# OmniBot_motor_driver.net
KiCad netlist of a schematic drawn in EAGLE
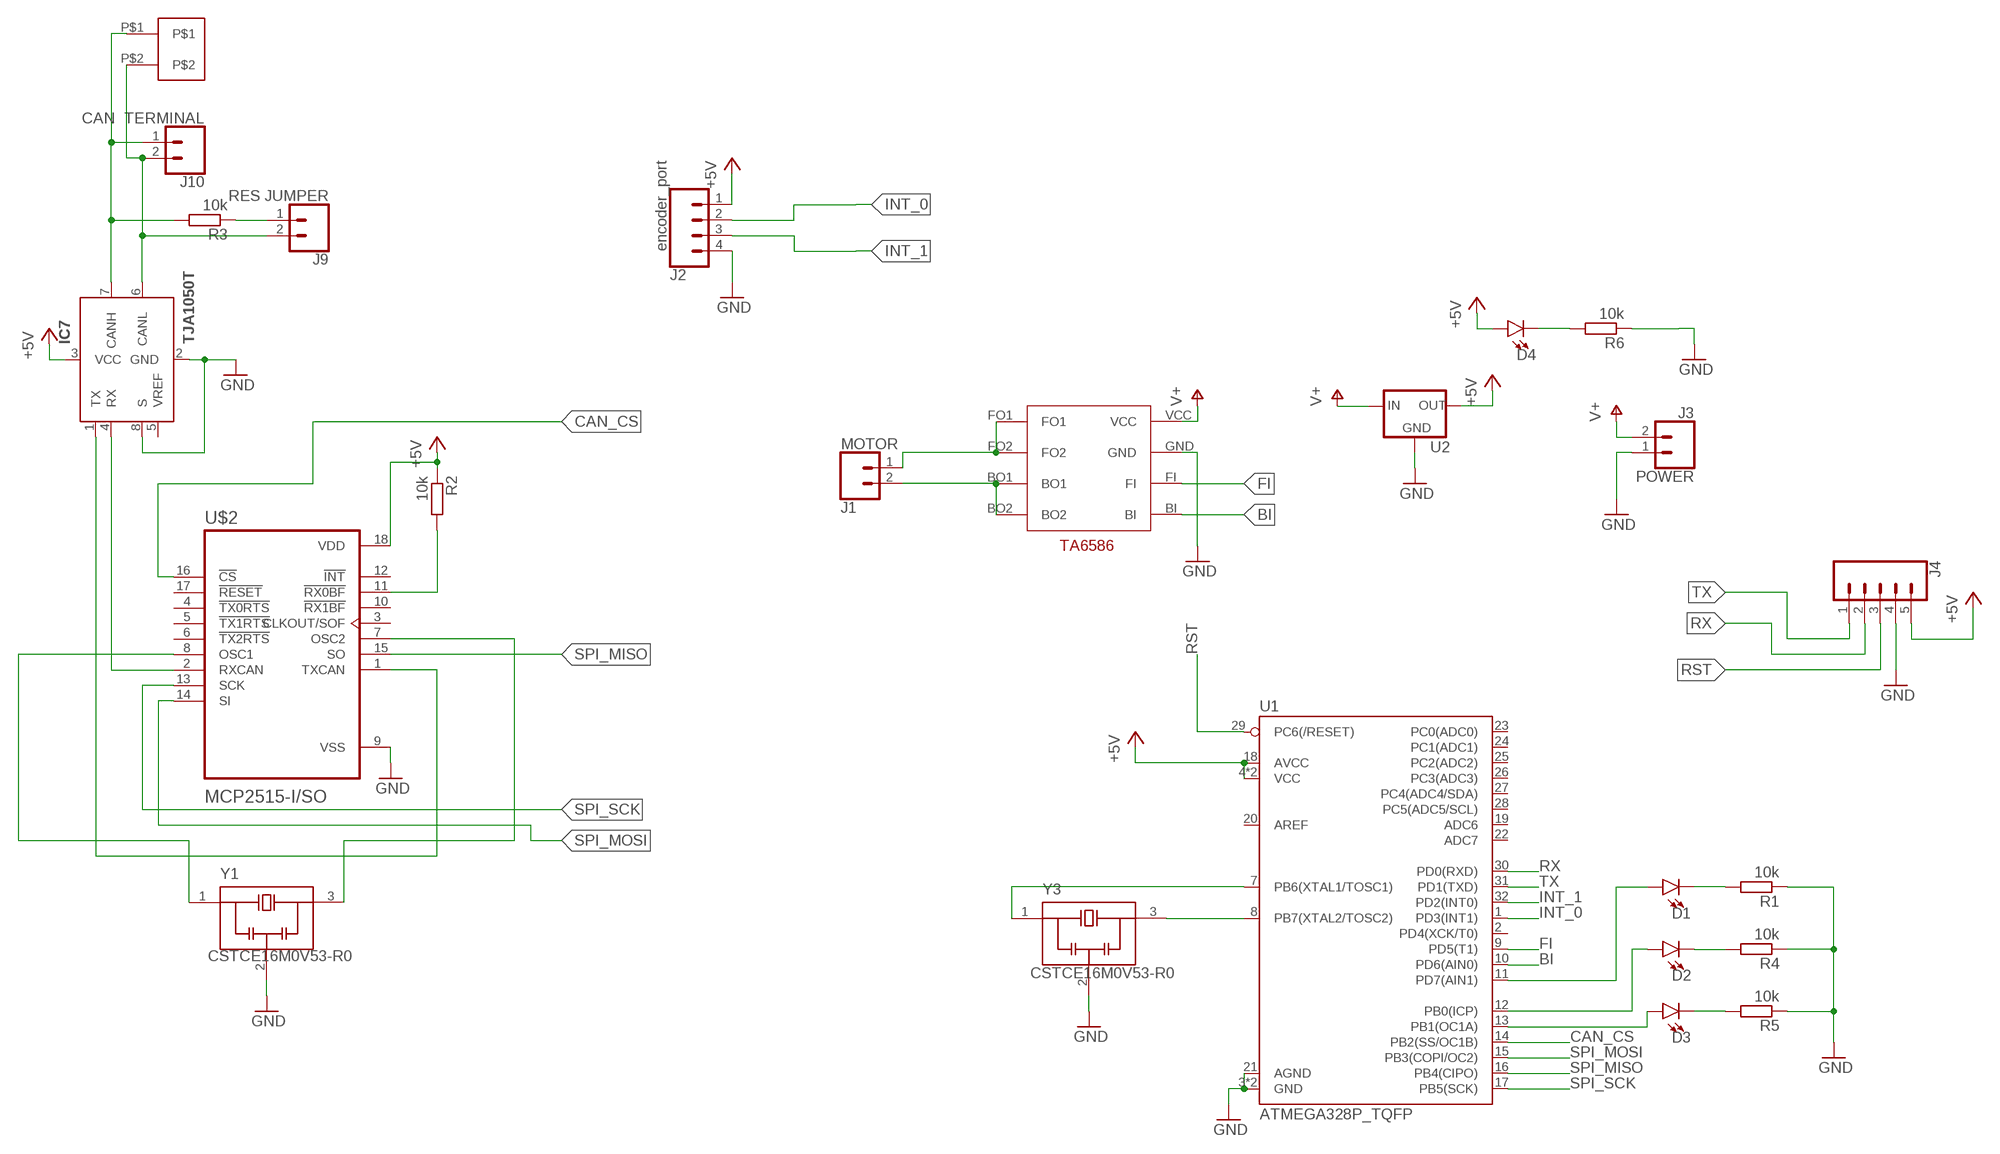
[diagram p0: schematic, sheet 1]

(export (version "E")
  (design (tool "Eeschema 10.0.6"))
  (components
    (comp (ref "D1")
      (value "LED3MM")
      (footprint "eagle-import:LED_3MM")
      (libsource (lib "eagle-import") (part "LED3MM"))
    )
    (comp (ref "D2")
      (value "LED3MM")
      (footprint "eagle-import:LED_3MM")
      (libsource (lib "eagle-import") (part "LED3MM"))
    )
    (comp (ref "D3")
      (value "LED3MM")
      (footprint "eagle-import:LED_3MM")
      (libsource (lib "eagle-import") (part "LED3MM"))
    )
    (comp (ref "D4")
      (value "LED3MM")
      (footprint "eagle-import:LED_3MM")
      (libsource (lib "eagle-import") (part "LED3MM"))
    )
    (comp (ref "IC7")
      (value "TJA1050T")
      (footprint "eagle-import:SOIC8")
      (fields (field (name "MF") "NXP"))
      (libsource (lib "eagle-import") (part "TJA1050T"))
    )
    (comp (ref "J1")
      (value "MOTOR")
      (footprint "eagle-import:SCREWTERMINAL-5MM-2")
      (libsource (lib "eagle-import") (part "CONN_025MM"))
    )
    (comp (ref "J2")
      (value "encoder_port")
      (footprint "eagle-import:MOLEX-1X4")
      (libsource (lib "eagle-import") (part "CONN_04POLAR"))
    )
    (comp (ref "J3")
      (value "POWER")
      (footprint "eagle-import:SCREWTERMINAL-5MM-2")
      (libsource (lib "eagle-import") (part "CONN_025MM"))
    )
    (comp (ref "J4")
      (value "CONN_05PTH")
      (footprint "eagle-import:1X05")
      (libsource (lib "eagle-import") (part "CONN_05PTH"))
    )
    (comp (ref "J9")
      (value "RES JUMPER")
      (footprint "eagle-import:1X02")
      (libsource (lib "eagle-import") (part "CONN_02"))
    )
    (comp (ref "J10")
      (value "CAN TERMINAL")
      (footprint "eagle-import:SCREWTERMINAL-5MM-2")
      (libsource (lib "eagle-import") (part "CONN_025MM"))
    )
    (comp (ref "R1")
      (value "10k")
      (footprint "eagle-import:R0805")
      (libsource (lib "eagle-import") (part "R-EU_R0805"))
    )
    (comp (ref "R2")
      (value "10k")
      (footprint "eagle-import:R0805")
      (libsource (lib "eagle-import") (part "R-EU_R0805"))
    )
    (comp (ref "R3")
      (value "10k")
      (footprint "eagle-import:R0805")
      (libsource (lib "eagle-import") (part "R-EU_R0805"))
    )
    (comp (ref "R4")
      (value "10k")
      (footprint "eagle-import:R0805")
      (libsource (lib "eagle-import") (part "R-EU_R0805"))
    )
    (comp (ref "R5")
      (value "10k")
      (footprint "eagle-import:R0805")
      (libsource (lib "eagle-import") (part "R-EU_R0805"))
    )
    (comp (ref "R6")
      (value "10k")
      (footprint "eagle-import:R0805")
      (libsource (lib "eagle-import") (part "R-EU_R0805"))
    )
    (comp (ref "U$1")
      (value "15EDGRC-3.5-2P")
      (footprint "eagle-import:15EDGRC-3.5-2P-PAK")
      (fields (field (name "MF") "Degson") (field (name "MP") "15EDGRC-3.5/2P"))
      (libsource (lib "eagle-import") (part "15EDGRC-3.5-2P"))
    )
    (comp (ref "U$2")
      (value "MCP2515-I/SO")
      (footprint "eagle-import:SOIC127P1030X265-18N")
      (fields (field (name "MF") "Microchip"))
      (libsource (lib "eagle-import") (part "MCP2515-I/SO"))
    )
    (comp (ref "U$3")
      (value "TA6586")
      (footprint "eagle-import:TA6586-FOOTPRINT")
      (fields (field (name "MF") "Wuxi"))
      (libsource (lib "eagle-import") (part "TA6586"))
    )
    (comp (ref "U1")
      (value "ATMEGA328P_TQFP")
      (footprint "eagle-import:TQFP32-08")
      (libsource (lib "eagle-import") (part "ATMEGA328P_TQFP"))
    )
    (comp (ref "U2")
      (value "V_REG_78XXSINK")
      (footprint "eagle-import:TO220-IGO")
      (libsource (lib "eagle-import") (part "V_REG_78XXSINK"))
    )
    (comp (ref "Y1")
      (value "CSTCE16M0V53-R0")
      (footprint "eagle-import:OSC_CSTCE16M0V53-R0")
      (fields (field (name "MF") "Murata"))
      (libsource (lib "eagle-import") (part "CSTCE16M0V53-R0"))
    )
    (comp (ref "Y3")
      (value "CSTCE16M0V53-R0")
      (footprint "eagle-import:OSC_CSTCE16M0V53-R0")
      (fields (field (name "MF") "Murata"))
      (libsource (lib "eagle-import") (part "CSTCE16M0V53-R0"))
    )
  )
  (nets
    (net (code "1") (name "+5V") (class "Default")
      (node (ref "D4") (pin "A") (pinfunction "A_A") (pintype "passive"))
      (node (ref "IC7") (pin "3") (pinfunction "VCC_3") (pintype "input"))
      (node (ref "J2") (pin "1") (pinfunction "1_1") (pintype "passive"))
      (node (ref "J4") (pin "5") (pinfunction "5_5") (pintype "passive"))
      (node (ref "R2") (pin "1") (pinfunction "1_1") (pintype "passive"))
      (node (ref "U$2") (pin "18") (pinfunction "VDD_18") (pintype "power_in"))
      (node (ref "U1") (pin "18") (pinfunction "AVCC_18") (pintype "bidirectional"))
      (node (ref "U1") (pin "4") (pinfunction "VCC_4") (pintype "bidirectional"))
      (node (ref "U1") (pin "6") (pinfunction "VCC_6") (pintype "bidirectional"))
      (node (ref "U2") (pin "OUT") (pinfunction "OUT_OUT") (pintype "passive"))
    )
    (net (code "2") (name "BI") (class "Default")
      (node (ref "U$3") (pin "BI") (pinfunction "BI_BI") (pintype "bidirectional"))
      (node (ref "U1") (pin "10") (pinfunction "PD6(AIN0)_10") (pintype "bidirectional"))
    )
    (net (code "3") (name "CAN_CS") (class "Default")
      (node (ref "U$2") (pin "16") (pinfunction "~{CS}_16") (pintype "input"))
      (node (ref "U1") (pin "14") (pinfunction "PB2(SS/OC1B)_14") (pintype "bidirectional"))
    )
    (net (code "4") (name "FI") (class "Default")
      (node (ref "U$3") (pin "FI") (pinfunction "FI_FI") (pintype "bidirectional"))
      (node (ref "U1") (pin "9") (pinfunction "PD5(T1)_9") (pintype "bidirectional"))
    )
    (net (code "5") (name "GND") (class "Default")
      (node (ref "IC7") (pin "2") (pinfunction "GND_2") (pintype "power_in"))
      (node (ref "IC7") (pin "8") (pinfunction "S_8") (pintype "input"))
      (node (ref "J2") (pin "4") (pinfunction "4_4") (pintype "passive"))
      (node (ref "J3") (pin "1") (pinfunction "1_1") (pintype "passive"))
      (node (ref "J4") (pin "4") (pinfunction "4_4") (pintype "passive"))
      (node (ref "R1") (pin "1") (pinfunction "1_1") (pintype "passive"))
      (node (ref "R4") (pin "1") (pinfunction "1_1") (pintype "passive"))
      (node (ref "R5") (pin "1") (pinfunction "1_1") (pintype "passive"))
      (node (ref "R6") (pin "1") (pinfunction "1_1") (pintype "passive"))
      (node (ref "U$2") (pin "9") (pinfunction "VSS_9") (pintype "power_in"))
      (node (ref "U$3") (pin "GND") (pinfunction "GND_GND") (pintype "bidirectional"))
      (node (ref "U1") (pin "21") (pinfunction "AGND_21") (pintype "bidirectional"))
      (node (ref "U1") (pin "3") (pinfunction "GND_3") (pintype "bidirectional"))
      (node (ref "U1") (pin "5") (pinfunction "GND_5") (pintype "bidirectional"))
      (node (ref "U2") (pin "GND") (pinfunction "GND_GND") (pintype "input"))
      (node (ref "Y1") (pin "2") (pinfunction "GND_2") (pintype "power_in"))
      (node (ref "Y3") (pin "2") (pinfunction "GND_2") (pintype "power_in"))
    )
    (net (code "6") (name "INT_0") (class "Default")
      (node (ref "J2") (pin "2") (pinfunction "2_2") (pintype "passive"))
      (node (ref "U1") (pin "1") (pinfunction "PD3(INT1)_1") (pintype "bidirectional"))
    )
    (net (code "7") (name "INT_1") (class "Default")
      (node (ref "J2") (pin "3") (pinfunction "3_3") (pintype "passive"))
      (node (ref "U1") (pin "32") (pinfunction "PD2(INT0)_32") (pintype "bidirectional"))
    )
    (net (code "8") (name "Net-(D1-C)") (class "Default")
      (node (ref "D1") (pin "K") (pinfunction "C_K") (pintype "passive"))
      (node (ref "R1") (pin "2") (pinfunction "2_2") (pintype "passive"))
    )
    (net (code "9") (name "Net-(D2-C)") (class "Default")
      (node (ref "D2") (pin "K") (pinfunction "C_K") (pintype "passive"))
      (node (ref "R4") (pin "2") (pinfunction "2_2") (pintype "passive"))
    )
    (net (code "10") (name "Net-(D3-C)") (class "Default")
      (node (ref "D3") (pin "K") (pinfunction "C_K") (pintype "passive"))
      (node (ref "R5") (pin "2") (pinfunction "2_2") (pintype "passive"))
    )
    (net (code "11") (name "Net-(D4-C)") (class "Default")
      (node (ref "D4") (pin "K") (pinfunction "C_K") (pintype "passive"))
      (node (ref "R6") (pin "2") (pinfunction "2_2") (pintype "passive"))
    )
    (net (code "12") (name "Net-(IC7-CANH)") (class "Default")
      (node (ref "IC7") (pin "7") (pinfunction "CANH_7") (pintype "bidirectional"))
      (node (ref "J10") (pin "1") (pinfunction "1_1") (pintype "passive"))
      (node (ref "R3") (pin "2") (pinfunction "2_2") (pintype "passive"))
      (node (ref "U$1") (pin "P$1") (pinfunction "P$1_P$1") (pintype "bidirectional"))
    )
    (net (code "13") (name "Net-(IC7-CANL)") (class "Default")
      (node (ref "IC7") (pin "6") (pinfunction "CANL_6") (pintype "bidirectional"))
      (node (ref "J10") (pin "2") (pinfunction "2_2") (pintype "passive"))
      (node (ref "J9") (pin "2") (pinfunction "2_2") (pintype "passive"))
      (node (ref "U$1") (pin "P$2") (pinfunction "P$2_P$2") (pintype "bidirectional"))
    )
    (net (code "14") (name "Net-(IC7-RX)") (class "Default")
      (node (ref "IC7") (pin "4") (pinfunction "RX_4") (pintype "output"))
      (node (ref "U$2") (pin "2") (pinfunction "RXCAN_2") (pintype "input"))
    )
    (net (code "15") (name "Net-(IC7-TX)") (class "Default")
      (node (ref "IC7") (pin "1") (pinfunction "TX_1") (pintype "input"))
      (node (ref "U$2") (pin "1") (pinfunction "TXCAN_1") (pintype "output"))
    )
    (net (code "16") (name "Net-(J1-Pad1)") (class "Default")
      (node (ref "J1") (pin "1") (pinfunction "1_1") (pintype "passive"))
      (node (ref "U$3") (pin "FO1") (pinfunction "FO1_FO1") (pintype "bidirectional"))
      (node (ref "U$3") (pin "FO2") (pinfunction "FO2_FO2") (pintype "bidirectional"))
    )
    (net (code "17") (name "Net-(J1-Pad2)") (class "Default")
      (node (ref "J1") (pin "2") (pinfunction "2_2") (pintype "passive"))
      (node (ref "U$3") (pin "BO1") (pinfunction "BO1_BO1") (pintype "bidirectional"))
      (node (ref "U$3") (pin "BO2") (pinfunction "BO2_BO2") (pintype "bidirectional"))
    )
    (net (code "18") (name "Net-(J9-Pad1)") (class "Default")
      (node (ref "J9") (pin "1") (pinfunction "1_1") (pintype "passive"))
      (node (ref "R3") (pin "1") (pinfunction "1_1") (pintype "passive"))
    )
    (net (code "19") (name "Net-(U$2-OSC1)") (class "Default")
      (node (ref "U$2") (pin "8") (pinfunction "OSC1_8") (pintype "input"))
      (node (ref "Y1") (pin "1") (pinfunction "IN_1") (pintype "input"))
    )
    (net (code "20") (name "Net-(U$2-OSC2)") (class "Default")
      (node (ref "U$2") (pin "7") (pinfunction "OSC2_7") (pintype "output"))
      (node (ref "Y1") (pin "3") (pinfunction "OUT_3") (pintype "output"))
    )
    (net (code "21") (name "Net-(U$2-~{RX0BF})") (class "Default")
      (node (ref "R2") (pin "2") (pinfunction "2_2") (pintype "passive"))
      (node (ref "U$2") (pin "11") (pinfunction "~{RX0BF}_11") (pintype "output"))
    )
    (net (code "22") (name "Net-(U1-PB0(ICP))") (class "Default")
      (node (ref "D2") (pin "A") (pinfunction "A_A") (pintype "passive"))
      (node (ref "U1") (pin "12") (pinfunction "PB0(ICP)_12") (pintype "bidirectional"))
    )
    (net (code "23") (name "Net-(U1-PB1(OC1A))") (class "Default")
      (node (ref "D3") (pin "A") (pinfunction "A_A") (pintype "passive"))
      (node (ref "U1") (pin "13") (pinfunction "PB1(OC1A)_13") (pintype "bidirectional"))
    )
    (net (code "24") (name "Net-(U1-PB6(XTAL1{slash}TOSC1))") (class "Default")
      (node (ref "U1") (pin "7") (pinfunction "PB6(XTAL1/TOSC1)_7") (pintype "bidirectional"))
      (node (ref "Y3") (pin "1") (pinfunction "IN_1") (pintype "input"))
    )
    (net (code "25") (name "Net-(U1-PB7(XTAL2{slash}TOSC2))") (class "Default")
      (node (ref "U1") (pin "8") (pinfunction "PB7(XTAL2/TOSC2)_8") (pintype "bidirectional"))
      (node (ref "Y3") (pin "3") (pinfunction "OUT_3") (pintype "output"))
    )
    (net (code "26") (name "Net-(U1-PD7(AIN1))") (class "Default")
      (node (ref "D1") (pin "A") (pinfunction "A_A") (pintype "passive"))
      (node (ref "U1") (pin "11") (pinfunction "PD7(AIN1)_11") (pintype "bidirectional"))
    )
    (net (code "27") (name "RST") (class "Default")
      (node (ref "J4") (pin "3") (pinfunction "3_3") (pintype "passive"))
      (node (ref "U1") (pin "29") (pinfunction "PC6(/RESET)_29") (pintype "bidirectional"))
    )
    (net (code "28") (name "RX") (class "Default")
      (node (ref "J4") (pin "2") (pinfunction "2_2") (pintype "passive"))
      (node (ref "U1") (pin "30") (pinfunction "PD0(RXD)_30") (pintype "bidirectional"))
    )
    (net (code "29") (name "SPI_MISO") (class "Default")
      (node (ref "U$2") (pin "15") (pinfunction "SO_15") (pintype "output"))
      (node (ref "U1") (pin "16") (pinfunction "PB4(CIPO)_16") (pintype "bidirectional"))
    )
    (net (code "30") (name "SPI_MOSI") (class "Default")
      (node (ref "U$2") (pin "14") (pinfunction "SI_14") (pintype "input"))
      (node (ref "U1") (pin "15") (pinfunction "PB3(COPI/OC2)_15") (pintype "bidirectional"))
    )
    (net (code "31") (name "SPI_SCK") (class "Default")
      (node (ref "U$2") (pin "13") (pinfunction "SCK_13") (pintype "input"))
      (node (ref "U1") (pin "17") (pinfunction "PB5(SCK)_17") (pintype "bidirectional"))
    )
    (net (code "32") (name "TX") (class "Default")
      (node (ref "J4") (pin "1") (pinfunction "1_1") (pintype "passive"))
      (node (ref "U1") (pin "31") (pinfunction "PD1(TXD)_31") (pintype "bidirectional"))
    )
    (net (code "33") (name "V+") (class "Default")
      (node (ref "J3") (pin "2") (pinfunction "2_2") (pintype "passive"))
      (node (ref "U$3") (pin "VCC") (pinfunction "VCC_VCC") (pintype "bidirectional"))
      (node (ref "U2") (pin "IN") (pinfunction "IN_IN") (pintype "input"))
    )
    (net (code "34") (name "unconnected-(IC7-VREF-Pad5)") (class "Default")
      (node (ref "IC7") (pin "5") (pinfunction "VREF_5") (pintype "output"))
    )
    (net (code "35") (name "unconnected-(U$2-CLKOUT{slash}SOF-Pad3)") (class "Default")
      (node (ref "U$2") (pin "3") (pinfunction "CLKOUT/SOF_3") (pintype "output"))
    )
    (net (code "36") (name "unconnected-(U$2-~{INT}-Pad12)") (class "Default")
      (node (ref "U$2") (pin "12") (pinfunction "~{INT}_12") (pintype "output"))
    )
    (net (code "37") (name "unconnected-(U$2-~{RESET}-Pad17)") (class "Default")
      (node (ref "U$2") (pin "17") (pinfunction "~{RESET}_17") (pintype "input"))
    )
    (net (code "38") (name "unconnected-(U$2-~{RX1BF}-Pad10)") (class "Default")
      (node (ref "U$2") (pin "10") (pinfunction "~{RX1BF}_10") (pintype "output"))
    )
    (net (code "39") (name "unconnected-(U$2-~{TX0RTS}-Pad4)") (class "Default")
      (node (ref "U$2") (pin "4") (pinfunction "~{TX0RTS}_4") (pintype "input"))
    )
    (net (code "40") (name "unconnected-(U$2-~{TX1RTS}-Pad5)") (class "Default")
      (node (ref "U$2") (pin "5") (pinfunction "~{TX1RTS}_5") (pintype "input"))
    )
    (net (code "41") (name "unconnected-(U$2-~{TX2RTS}-Pad6)") (class "Default")
      (node (ref "U$2") (pin "6") (pinfunction "~{TX2RTS}_6") (pintype "input"))
    )
    (net (code "42") (name "unconnected-(U1-ADC6-Pad19)") (class "Default")
      (node (ref "U1") (pin "19") (pinfunction "ADC6_19") (pintype "bidirectional"))
    )
    (net (code "43") (name "unconnected-(U1-ADC7-Pad22)") (class "Default")
      (node (ref "U1") (pin "22") (pinfunction "ADC7_22") (pintype "bidirectional"))
    )
    (net (code "44") (name "unconnected-(U1-AREF-Pad20)") (class "Default")
      (node (ref "U1") (pin "20") (pinfunction "AREF_20") (pintype "bidirectional"))
    )
    (net (code "45") (name "unconnected-(U1-PC0(ADC0)-Pad23)") (class "Default")
      (node (ref "U1") (pin "23") (pinfunction "PC0(ADC0)_23") (pintype "bidirectional"))
    )
    (net (code "46") (name "unconnected-(U1-PC1(ADC1)-Pad24)") (class "Default")
      (node (ref "U1") (pin "24") (pinfunction "PC1(ADC1)_24") (pintype "bidirectional"))
    )
    (net (code "47") (name "unconnected-(U1-PC2(ADC2)-Pad25)") (class "Default")
      (node (ref "U1") (pin "25") (pinfunction "PC2(ADC2)_25") (pintype "bidirectional"))
    )
    (net (code "48") (name "unconnected-(U1-PC3(ADC3)-Pad26)") (class "Default")
      (node (ref "U1") (pin "26") (pinfunction "PC3(ADC3)_26") (pintype "bidirectional"))
    )
    (net (code "49") (name "unconnected-(U1-PC4(ADC4{slash}SDA)-Pad27)") (class "Default")
      (node (ref "U1") (pin "27") (pinfunction "PC4(ADC4/SDA)_27") (pintype "bidirectional"))
    )
    (net (code "50") (name "unconnected-(U1-PC5(ADC5{slash}SCL)-Pad28)") (class "Default")
      (node (ref "U1") (pin "28") (pinfunction "PC5(ADC5/SCL)_28") (pintype "bidirectional"))
    )
    (net (code "51") (name "unconnected-(U1-PD4(XCK{slash}T0)-Pad2)") (class "Default")
      (node (ref "U1") (pin "2") (pinfunction "PD4(XCK/T0)_2") (pintype "bidirectional"))
    )
  )
)
